# Adafruit_I2C_QT_Rotary_Encoder.net
KiCad netlist of a schematic drawn in EAGLE
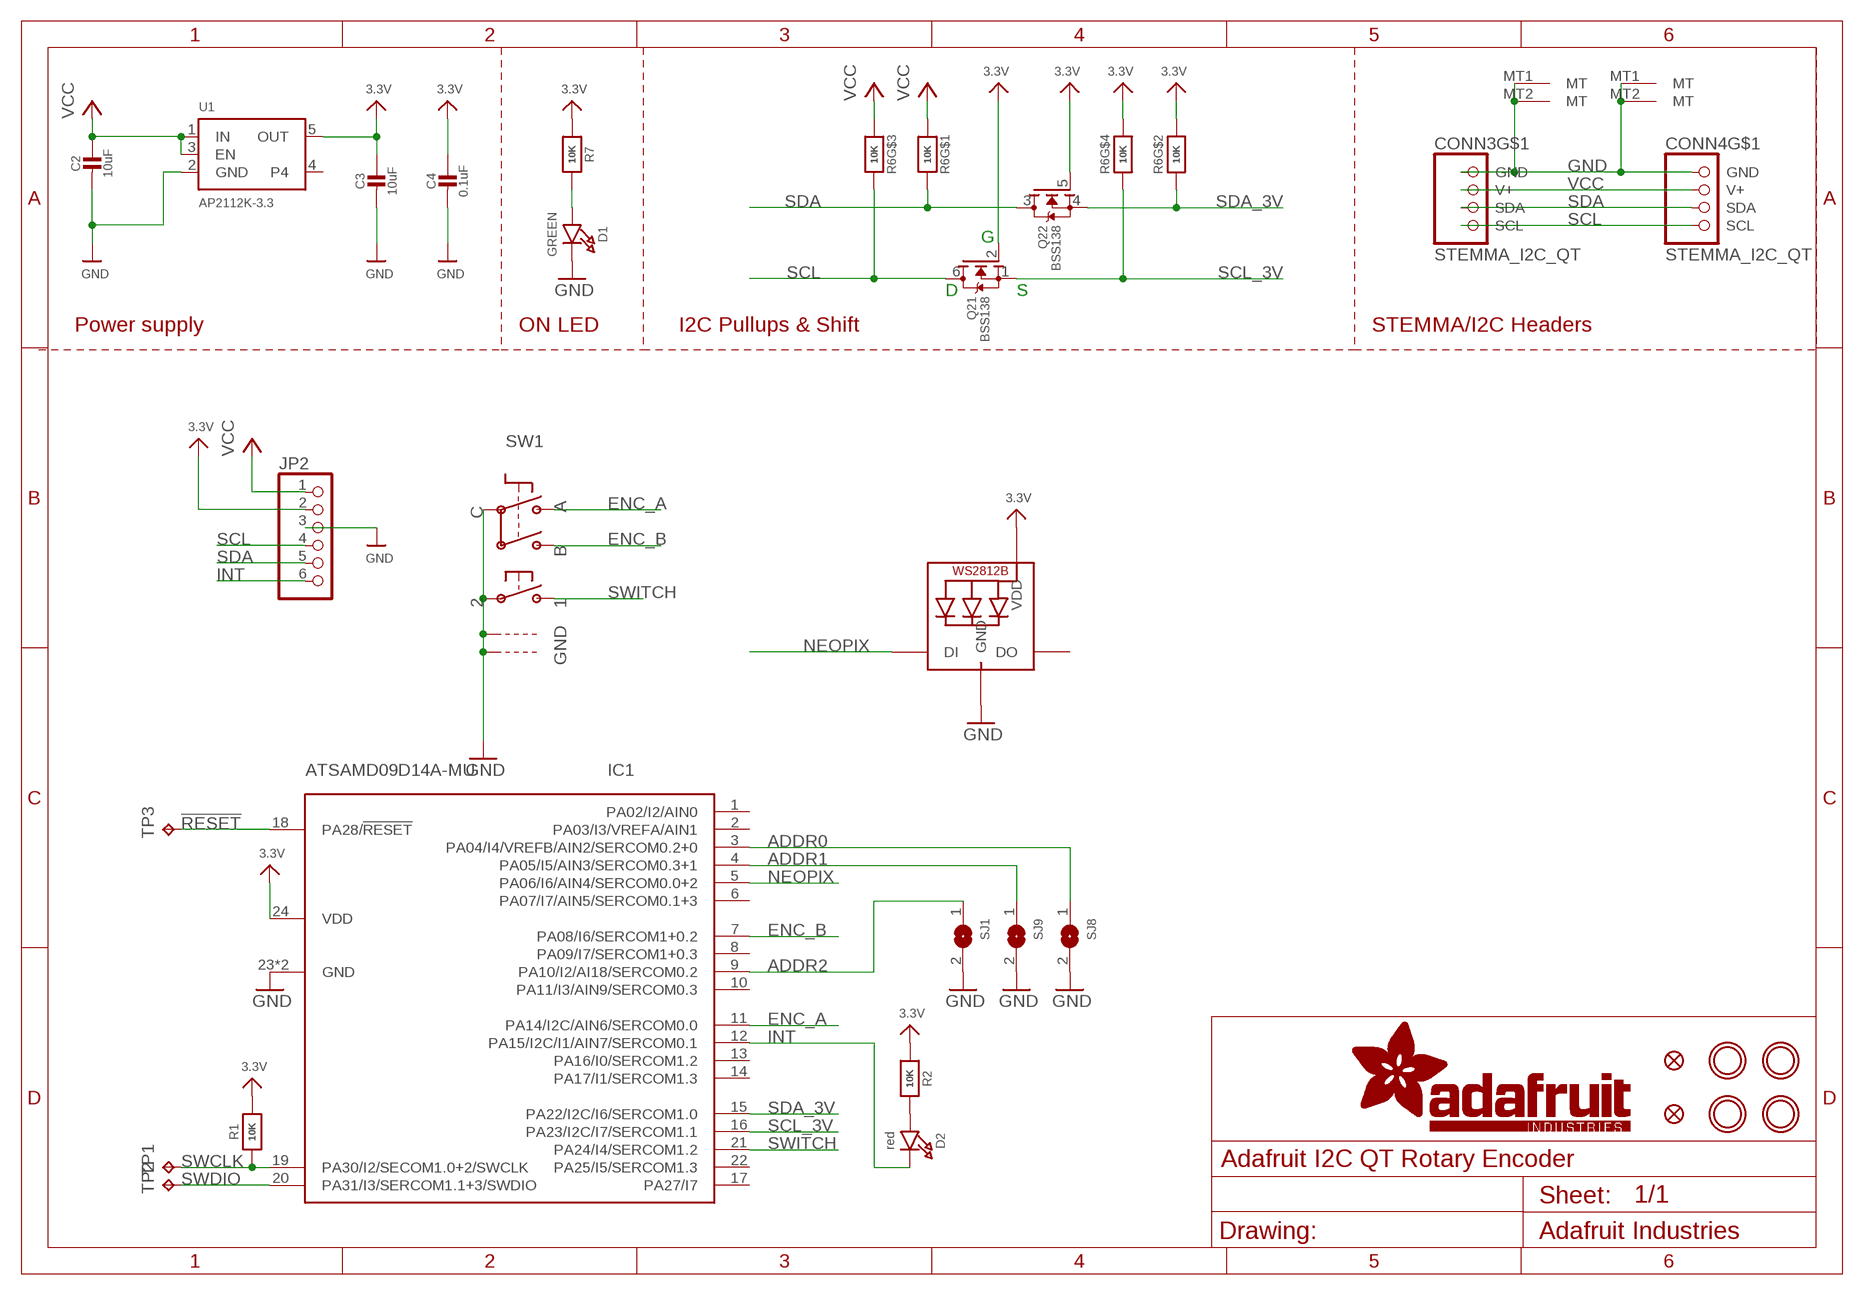
[diagram p0: schematic, sheet 1]

(export (version "E")
  (design (tool "Eeschema 10.0.6"))
  (components
    (comp (ref "C2")
      (value "10uF")
      (footprint "eagle-import:0805-NO")
      (libsource (lib "eagle-import") (part "CAP_CERAMIC0805-NOOUTLINE"))
    )
    (comp (ref "C3")
      (value "10uF")
      (footprint "eagle-import:0805-NO")
      (libsource (lib "eagle-import") (part "CAP_CERAMIC0805-NOOUTLINE"))
    )
    (comp (ref "C4")
      (value "0.1uF")
      (footprint "eagle-import:0603-NO")
      (libsource (lib "eagle-import") (part "CAP_CERAMIC0603_NO"))
    )
    (comp (ref "CONN3")
      (value "STEMMA_I2C_QT")
      (footprint "eagle-import:JST_SH4")
      (libsource (lib "eagle-import") (part "STEMMA_I2C_QT"))
    )
    (comp (ref "CONN4")
      (value "STEMMA_I2C_QT")
      (footprint "eagle-import:JST_SH4")
      (libsource (lib "eagle-import") (part "STEMMA_I2C_QT"))
    )
    (comp (ref "D1")
      (value "GREEN")
      (footprint "eagle-import:CHIPLED_0603_NOOUTLINE")
      (libsource (lib "eagle-import") (part "LED0603_NOOUTLINE"))
    )
    (comp (ref "D2")
      (value "red")
      (footprint "eagle-import:CHIPLED_0603_NOOUTLINE")
      (libsource (lib "eagle-import") (part "LED0603_NOOUTLINE"))
    )
    (comp (ref "FID3")
      (value "FIDUCIAL_1MM")
      (footprint "eagle-import:FIDUCIAL_1MM")
      (libsource (lib "eagle-import") (part "FIDUCIAL_1MM"))
    )
    (comp (ref "FID4")
      (value "FIDUCIAL_1MM")
      (footprint "eagle-import:FIDUCIAL_1MM")
      (libsource (lib "eagle-import") (part "FIDUCIAL_1MM"))
    )
    (comp (ref "IC1")
      (value "ATSAMD09D14A-MU")
      (footprint "eagle-import:QFN24_4MM")
      (libsource (lib "eagle-import") (part "ATSAMD09D14A-MU"))
    )
    (comp (ref "JP2")
      (value "HEADER-1X670MIL")
      (footprint "eagle-import:1X06_ROUND_70")
      (libsource (lib "eagle-import") (part "HEADER-1X670MIL"))
    )
    (comp (ref "LED1")
      (value "WS2812B_SK6812E")
      (footprint "eagle-import:NEO3535_REVERSE")
      (libsource (lib "eagle-import") (part "WS2812B_SK6812E"))
    )
    (comp (ref "Q2")
      (value "BSS138")
      (footprint "eagle-import:SOT363")
      (libsource (lib "eagle-import") (part "MOSFET-N_DUAL"))
    )
    (comp (ref "R1")
      (value "10K")
      (footprint "eagle-import:0603-NO")
      (libsource (lib "eagle-import") (part "RESISTOR_0603_NOOUT"))
    )
    (comp (ref "R2")
      (value "10K")
      (footprint "eagle-import:0603-NO")
      (libsource (lib "eagle-import") (part "RESISTOR_0603_NOOUT"))
    )
    (comp (ref "R6")
      (value "10K")
      (footprint "eagle-import:RESPACK_4X0603")
      (libsource (lib "eagle-import") (part "RESISTOR_4PACK"))
    )
    (comp (ref "R7")
      (value "10K")
      (footprint "eagle-import:0603-NO")
      (libsource (lib "eagle-import") (part "RESISTOR_0603_NOOUT"))
    )
    (comp (ref "SJ1")
      (value "SOLDERJUMPER")
      (footprint "eagle-import:SOLDERJUMPER_ARROW_NOPASTE")
      (libsource (lib "eagle-import") (part "SOLDERJUMPER"))
    )
    (comp (ref "SJ8")
      (value "SOLDERJUMPER")
      (footprint "eagle-import:SOLDERJUMPER_ARROW_NOPASTE")
      (libsource (lib "eagle-import") (part "SOLDERJUMPER"))
    )
    (comp (ref "SJ9")
      (value "SOLDERJUMPER")
      (footprint "eagle-import:SOLDERJUMPER_ARROW_NOPASTE")
      (libsource (lib "eagle-import") (part "SOLDERJUMPER"))
    )
    (comp (ref "SW1")
      (value "ENCODER_PLUS_SWITCH_BOURNS_PEC11")
      (footprint "eagle-import:PEC11+SWITCH")
      (libsource (lib "eagle-import") (part "ENCODER_PLUS_SWITCH_PEC11_BOURNS"))
    )
    (comp (ref "TP1")
      (value "TPTP15R")
      (footprint "eagle-import:TP15R")
      (libsource (lib "eagle-import") (part "TPTP15R"))
    )
    (comp (ref "TP2")
      (value "TPTP15R")
      (footprint "eagle-import:TP15R")
      (libsource (lib "eagle-import") (part "TPTP15R"))
    )
    (comp (ref "TP3")
      (value "TPTP15R")
      (footprint "eagle-import:TP15R")
      (libsource (lib "eagle-import") (part "TPTP15R"))
    )
    (comp (ref "U$25")
      (value "MOUNTINGHOLE2.5")
      (footprint "eagle-import:MOUNTINGHOLE_2.5_PLATED")
      (libsource (lib "eagle-import") (part "MOUNTINGHOLE2.5"))
    )
    (comp (ref "U$27")
      (value "MOUNTINGHOLE2.5")
      (footprint "eagle-import:MOUNTINGHOLE_2.5_PLATED")
      (libsource (lib "eagle-import") (part "MOUNTINGHOLE2.5"))
    )
    (comp (ref "U$29")
      (value "MOUNTINGHOLE2.5")
      (footprint "eagle-import:MOUNTINGHOLE_2.5_PLATED")
      (libsource (lib "eagle-import") (part "MOUNTINGHOLE2.5"))
    )
    (comp (ref "U$30")
      (value "MOUNTINGHOLE2.5")
      (footprint "eagle-import:MOUNTINGHOLE_2.5_PLATED")
      (libsource (lib "eagle-import") (part "MOUNTINGHOLE2.5"))
    )
    (comp (ref "U1")
      (value "AP2112K-3.3")
      (footprint "eagle-import:SOT23-5")
      (libsource (lib "eagle-import") (part "VREG_SOT23-5"))
    )
  )
  (nets
    (net (code "1") (name "/ADDR0") (class "Default")
      (node (ref "IC1") (pin "3") (pinfunction "PA04/I4/VREFB/AIN2/SERCOM0.2+0_3") (pintype "bidirectional"))
      (node (ref "SJ8") (pin "1") (pinfunction "1_1") (pintype "passive"))
    )
    (net (code "2") (name "/ADDR1") (class "Default")
      (node (ref "IC1") (pin "4") (pinfunction "PA05/I5/AIN3/SERCOM0.3+1_4") (pintype "bidirectional"))
      (node (ref "SJ9") (pin "1") (pinfunction "1_1") (pintype "passive"))
    )
    (net (code "3") (name "/ADDR2") (class "Default")
      (node (ref "IC1") (pin "9") (pinfunction "PA10/I2/AI18/SERCOM0.2_9") (pintype "bidirectional"))
      (node (ref "SJ1") (pin "1") (pinfunction "1_1") (pintype "passive"))
    )
    (net (code "4") (name "/ENC_A") (class "Default")
      (node (ref "IC1") (pin "11") (pinfunction "PA14/I2C/AIN6/SERCOM0.0_11") (pintype "bidirectional"))
      (node (ref "SW1") (pin "P$A") (pinfunction "P$A_P$A") (pintype "passive"))
    )
    (net (code "5") (name "/ENC_B") (class "Default")
      (node (ref "IC1") (pin "7") (pinfunction "PA08/I6/SERCOM1+0.2_7") (pintype "bidirectional"))
      (node (ref "SW1") (pin "P$B") (pinfunction "P$B_P$B") (pintype "passive"))
    )
    (net (code "6") (name "/INT") (class "Default")
      (node (ref "D2") (pin "C") (pinfunction "C_C") (pintype "passive"))
      (node (ref "IC1") (pin "12") (pinfunction "PA15/I2C/I1/AIN7/SERCOM0.1_12") (pintype "bidirectional"))
      (node (ref "JP2") (pin "6") (pinfunction "6_6") (pintype "passive"))
    )
    (net (code "7") (name "/NEOPIX") (class "Default")
      (node (ref "IC1") (pin "5") (pinfunction "PA06/I6/AIN4/SERCOM0.0+2_5") (pintype "bidirectional"))
      (node (ref "LED1") (pin "4-DIN") (pinfunction "DI_4-DIN") (pintype "input"))
    )
    (net (code "8") (name "/SCL") (class "Default")
      (node (ref "CONN3") (pin "4") (pinfunction "SCL_4") (pintype "passive"))
      (node (ref "CONN4") (pin "4") (pinfunction "SCL_4") (pintype "passive"))
      (node (ref "JP2") (pin "4") (pinfunction "4_4") (pintype "passive"))
      (node (ref "Q2") (pin "6") (pinfunction "D_6") (pintype "bidirectional"))
      (node (ref "R6") (pin "6") (pinfunction "2_6") (pintype "passive"))
    )
    (net (code "9") (name "/SCL_3V") (class "Default")
      (node (ref "IC1") (pin "16") (pinfunction "PA23/I2C/I7/SERCOM1.1_16") (pintype "bidirectional"))
      (node (ref "Q2") (pin "1") (pinfunction "S_1") (pintype "bidirectional"))
      (node (ref "R6") (pin "5") (pinfunction "2_5") (pintype "passive"))
    )
    (net (code "10") (name "/SDA") (class "Default")
      (node (ref "CONN3") (pin "3") (pinfunction "SDA_3") (pintype "passive"))
      (node (ref "CONN4") (pin "3") (pinfunction "SDA_3") (pintype "passive"))
      (node (ref "JP2") (pin "5") (pinfunction "5_5") (pintype "passive"))
      (node (ref "Q2") (pin "3") (pinfunction "D_3") (pintype "bidirectional"))
      (node (ref "R6") (pin "8") (pinfunction "2_8") (pintype "passive"))
    )
    (net (code "11") (name "/SDA_3V") (class "Default")
      (node (ref "IC1") (pin "15") (pinfunction "PA22/I2C/I6/SERCOM1.0_15") (pintype "bidirectional"))
      (node (ref "Q2") (pin "4") (pinfunction "S_4") (pintype "bidirectional"))
      (node (ref "R6") (pin "7") (pinfunction "2_7") (pintype "passive"))
    )
    (net (code "12") (name "/SWCLK") (class "Default")
      (node (ref "IC1") (pin "19") (pinfunction "PA30/I2/SECOM1.0+2/SWCLK_19") (pintype "bidirectional"))
      (node (ref "R1") (pin "1") (pinfunction "1_1") (pintype "passive"))
      (node (ref "TP1") (pin "TP") (pinfunction "TP_TP") (pintype "input"))
    )
    (net (code "13") (name "/SWDIO") (class "Default")
      (node (ref "IC1") (pin "20") (pinfunction "PA31/I3/SERCOM1.1+3/SWDIO_20") (pintype "bidirectional"))
      (node (ref "TP2") (pin "TP") (pinfunction "TP_TP") (pintype "input"))
    )
    (net (code "14") (name "/SWITCH") (class "Default")
      (node (ref "IC1") (pin "21") (pinfunction "PA24/I4/SERCOM1.2_21") (pintype "bidirectional"))
      (node (ref "SW1") (pin "P$1") (pinfunction "P$1_P$1") (pintype "passive"))
    )
    (net (code "15") (name "/~{RESET}") (class "Default")
      (node (ref "IC1") (pin "18") (pinfunction "PA28/~{RESET}_18") (pintype "bidirectional"))
      (node (ref "TP3") (pin "TP") (pinfunction "TP_TP") (pintype "input"))
    )
    (net (code "16") (name "3.3V") (class "Default")
      (node (ref "C3") (pin "1") (pinfunction "1_1") (pintype "passive"))
      (node (ref "C4") (pin "1") (pinfunction "1_1") (pintype "passive"))
      (node (ref "IC1") (pin "24") (pinfunction "VDD_24") (pintype "power_in"))
      (node (ref "JP2") (pin "2") (pinfunction "2_2") (pintype "passive"))
      (node (ref "LED1") (pin "1-VDD") (pinfunction "VDD_1-VDD") (pintype "power_in"))
      (node (ref "Q2") (pin "2") (pinfunction "G_2") (pintype "bidirectional"))
      (node (ref "Q2") (pin "5") (pinfunction "G_5") (pintype "bidirectional"))
      (node (ref "R1") (pin "2") (pinfunction "2_2") (pintype "passive"))
      (node (ref "R2") (pin "1") (pinfunction "1_1") (pintype "passive"))
      (node (ref "R6") (pin "2") (pinfunction "1_2") (pintype "passive"))
      (node (ref "R6") (pin "4") (pinfunction "1_4") (pintype "passive"))
      (node (ref "R7") (pin "1") (pinfunction "1_1") (pintype "passive"))
      (node (ref "U1") (pin "5") (pinfunction "OUT_5") (pintype "power_in"))
    )
    (net (code "17") (name "GND") (class "Default")
      (node (ref "C2") (pin "2") (pinfunction "2_2") (pintype "passive"))
      (node (ref "C3") (pin "2") (pinfunction "2_2") (pintype "passive"))
      (node (ref "C4") (pin "2") (pinfunction "2_2") (pintype "passive"))
      (node (ref "CONN3") (pin "1") (pinfunction "GND_1") (pintype "passive"))
      (node (ref "CONN3") (pin "MT1") (pinfunction "MT_MT1") (pintype "bidirectional"))
      (node (ref "CONN3") (pin "MT2") (pinfunction "MT_MT2") (pintype "bidirectional"))
      (node (ref "CONN4") (pin "1") (pinfunction "GND_1") (pintype "passive"))
      (node (ref "CONN4") (pin "MT1") (pinfunction "MT_MT1") (pintype "bidirectional"))
      (node (ref "CONN4") (pin "MT2") (pinfunction "MT_MT2") (pintype "bidirectional"))
      (node (ref "D1") (pin "C") (pinfunction "C_C") (pintype "passive"))
      (node (ref "IC1") (pin "23") (pinfunction "GND_23") (pintype "power_in"))
      (node (ref "IC1") (pin "THERM") (pinfunction "GND_THERM") (pintype "power_in"))
      (node (ref "JP2") (pin "3") (pinfunction "3_3") (pintype "passive"))
      (node (ref "LED1") (pin "3-GND") (pinfunction "GND_3-GND") (pintype "power_in"))
      (node (ref "SJ1") (pin "2") (pinfunction "2_2") (pintype "passive"))
      (node (ref "SJ8") (pin "2") (pinfunction "2_2") (pintype "passive"))
      (node (ref "SJ9") (pin "2") (pinfunction "2_2") (pintype "passive"))
      (node (ref "SW1") (pin "P$2") (pinfunction "P$2_P$2") (pintype "passive"))
      (node (ref "SW1") (pin "P$C") (pinfunction "P$C_P$C") (pintype "passive"))
      (node (ref "SW1") (pin "P$GND1") (pinfunction "P$GND1_P$GND1") (pintype "passive"))
      (node (ref "SW1") (pin "P$GND2") (pinfunction "P$GND2_P$GND2") (pintype "passive"))
      (node (ref "U1") (pin "2") (pinfunction "GND_2") (pintype "power_in"))
    )
    (net (code "18") (name "Net-(D1-PadA)") (class "Default")
      (node (ref "D1") (pin "A") (pinfunction "A_A") (pintype "passive"))
      (node (ref "R7") (pin "2") (pinfunction "2_2") (pintype "passive"))
    )
    (net (code "19") (name "Net-(D2-PadA)") (class "Default")
      (node (ref "D2") (pin "A") (pinfunction "A_A") (pintype "passive"))
      (node (ref "R2") (pin "2") (pinfunction "2_2") (pintype "passive"))
    )
    (net (code "20") (name "VCC") (class "Default")
      (node (ref "C2") (pin "1") (pinfunction "1_1") (pintype "passive"))
      (node (ref "CONN3") (pin "2") (pinfunction "V+_2") (pintype "passive"))
      (node (ref "CONN4") (pin "2") (pinfunction "V+_2") (pintype "passive"))
      (node (ref "JP2") (pin "1") (pinfunction "1_1") (pintype "passive"))
      (node (ref "R6") (pin "1") (pinfunction "1_1") (pintype "passive"))
      (node (ref "R6") (pin "3") (pinfunction "1_3") (pintype "passive"))
      (node (ref "U1") (pin "1") (pinfunction "IN_1") (pintype "power_in"))
      (node (ref "U1") (pin "3") (pinfunction "EN_3") (pintype "input"))
    )
    (net (code "21") (name "unconnected-(IC1-PA02{slash}I2{slash}AIN0-Pad1)") (class "Default")
      (node (ref "IC1") (pin "1") (pinfunction "PA02/I2/AIN0_1") (pintype "bidirectional"))
    )
    (net (code "22") (name "unconnected-(IC1-PA03{slash}I3{slash}VREFA{slash}AIN1-Pad2)") (class "Default")
      (node (ref "IC1") (pin "2") (pinfunction "PA03/I3/VREFA/AIN1_2") (pintype "bidirectional"))
    )
    (net (code "23") (name "unconnected-(IC1-PA07{slash}I7{slash}AIN5{slash}SERCOM0.1+3-Pad6)") (class "Default")
      (node (ref "IC1") (pin "6") (pinfunction "PA07/I7/AIN5/SERCOM0.1+3_6") (pintype "bidirectional"))
    )
    (net (code "24") (name "unconnected-(IC1-PA09{slash}I7{slash}SERCOM1+0.3-Pad8)") (class "Default")
      (node (ref "IC1") (pin "8") (pinfunction "PA09/I7/SERCOM1+0.3_8") (pintype "bidirectional"))
    )
    (net (code "25") (name "unconnected-(IC1-PA11{slash}I3{slash}AIN9{slash}SERCOM0.3-Pad10)") (class "Default")
      (node (ref "IC1") (pin "10") (pinfunction "PA11/I3/AIN9/SERCOM0.3_10") (pintype "bidirectional"))
    )
    (net (code "26") (name "unconnected-(IC1-PA16{slash}I0{slash}SERCOM1.2-Pad13)") (class "Default")
      (node (ref "IC1") (pin "13") (pinfunction "PA16/I0/SERCOM1.2_13") (pintype "bidirectional"))
    )
    (net (code "27") (name "unconnected-(IC1-PA17{slash}I1{slash}SERCOM1.3-Pad14)") (class "Default")
      (node (ref "IC1") (pin "14") (pinfunction "PA17/I1/SERCOM1.3_14") (pintype "bidirectional"))
    )
    (net (code "28") (name "unconnected-(IC1-PA25{slash}I5{slash}SERCOM1.3-Pad22)") (class "Default")
      (node (ref "IC1") (pin "22") (pinfunction "PA25/I5/SERCOM1.3_22") (pintype "bidirectional"))
    )
    (net (code "29") (name "unconnected-(IC1-PA27{slash}I7-Pad17)") (class "Default")
      (node (ref "IC1") (pin "17") (pinfunction "PA27/I7_17") (pintype "bidirectional"))
    )
    (net (code "30") (name "unconnected-(LED1-DO-Pad2-DOUT)") (class "Default")
      (node (ref "LED1") (pin "2-DOUT") (pinfunction "DO_2-DOUT") (pintype "output"))
    )
    (net (code "31") (name "unconnected-(U1-P4-Pad4)") (class "Default")
      (node (ref "U1") (pin "4") (pinfunction "P4_4") (pintype "bidirectional"))
    )
  )
)
